# Mainland_revB.net
KiCad netlist of a schematic drawn in EAGLE
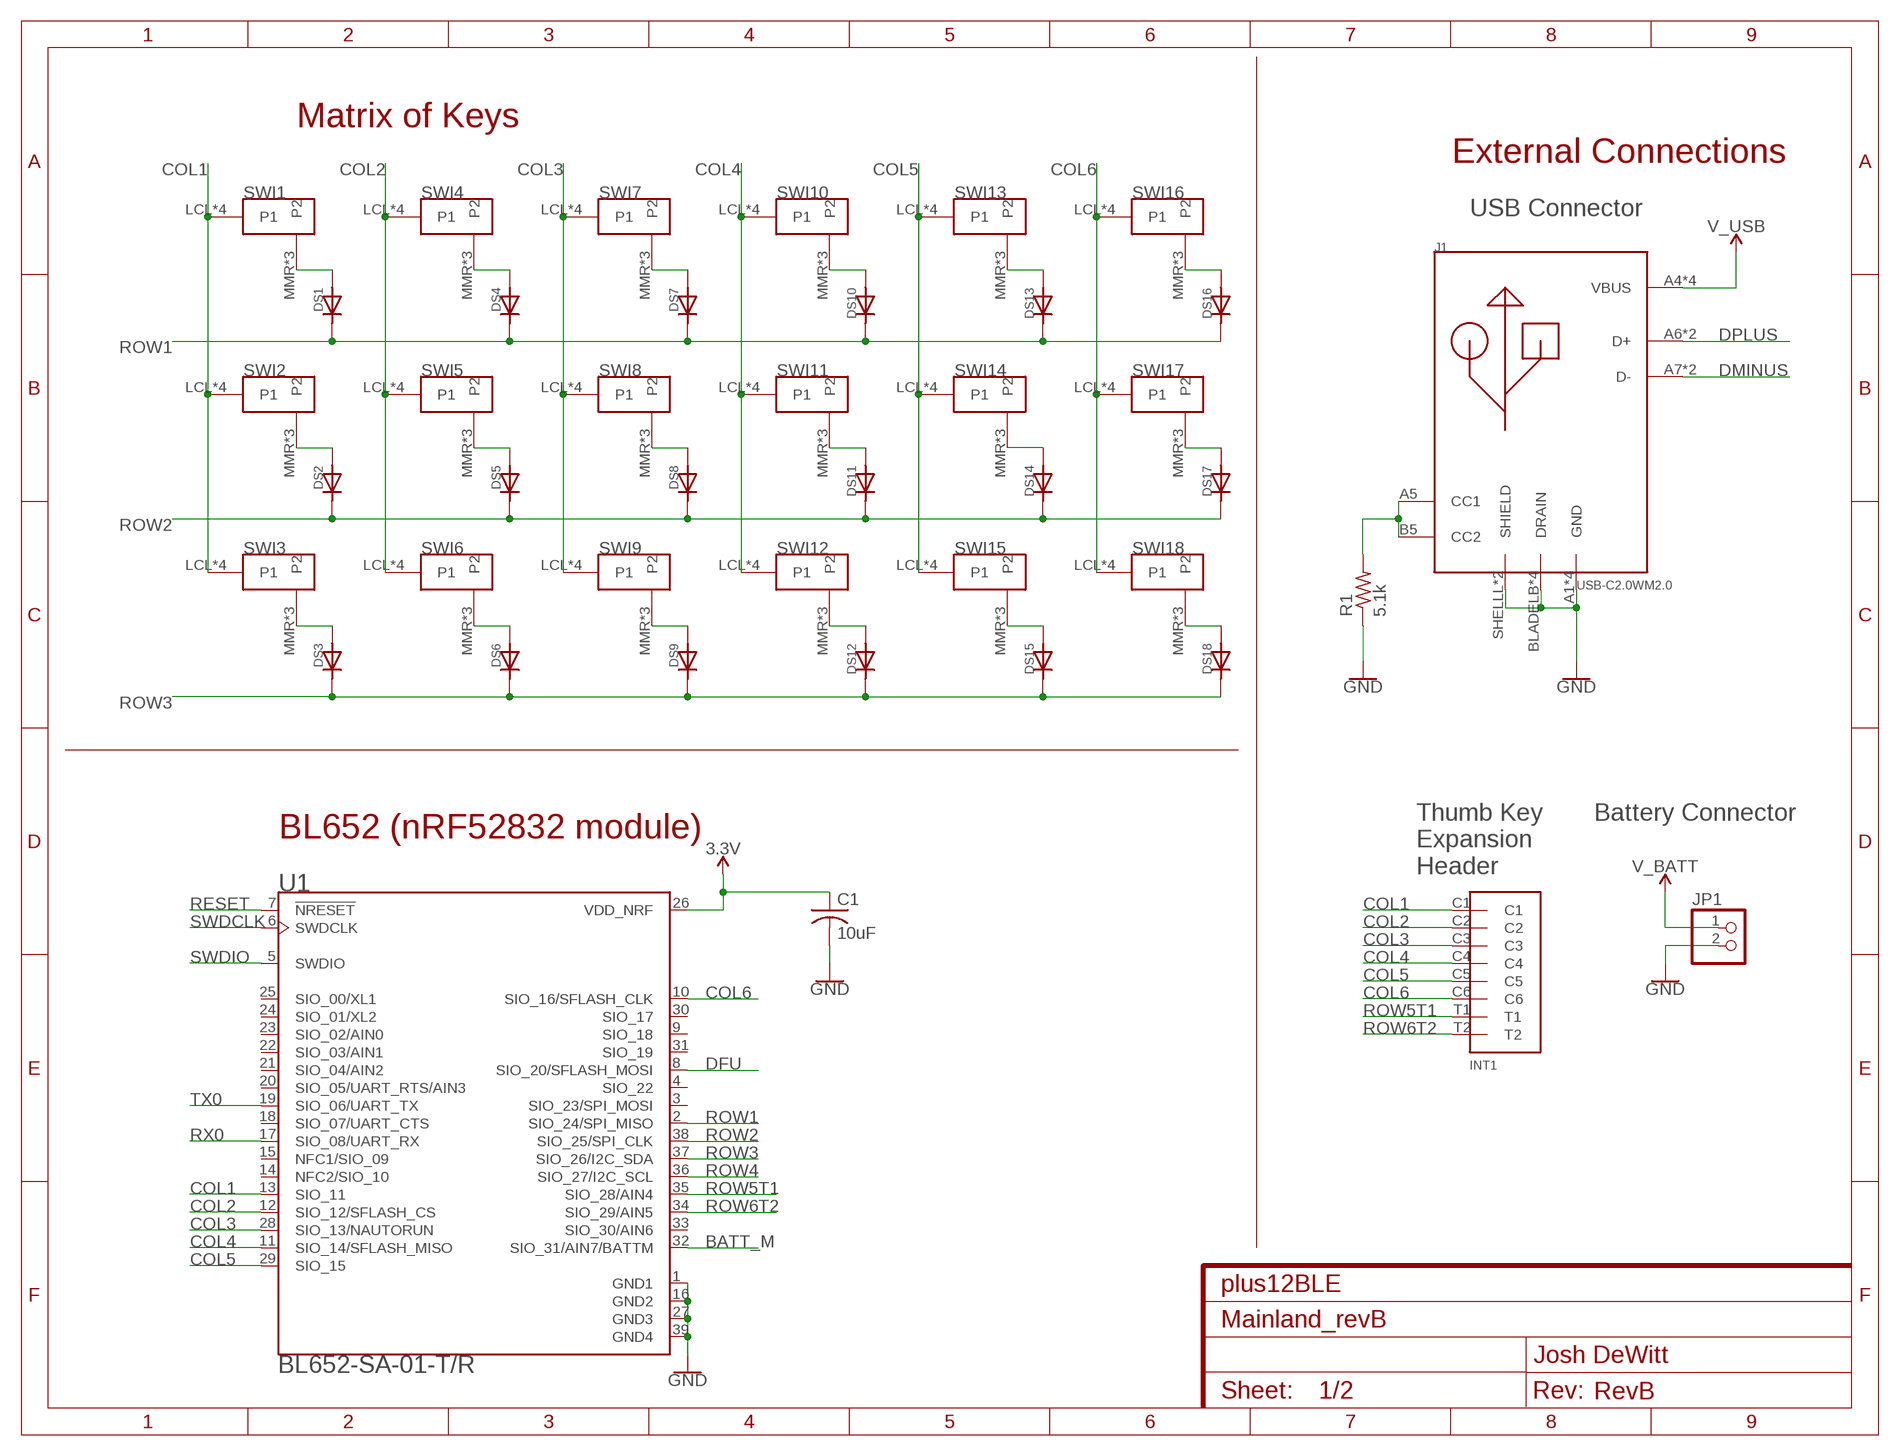
[diagram p0: schematic, sheet 1]
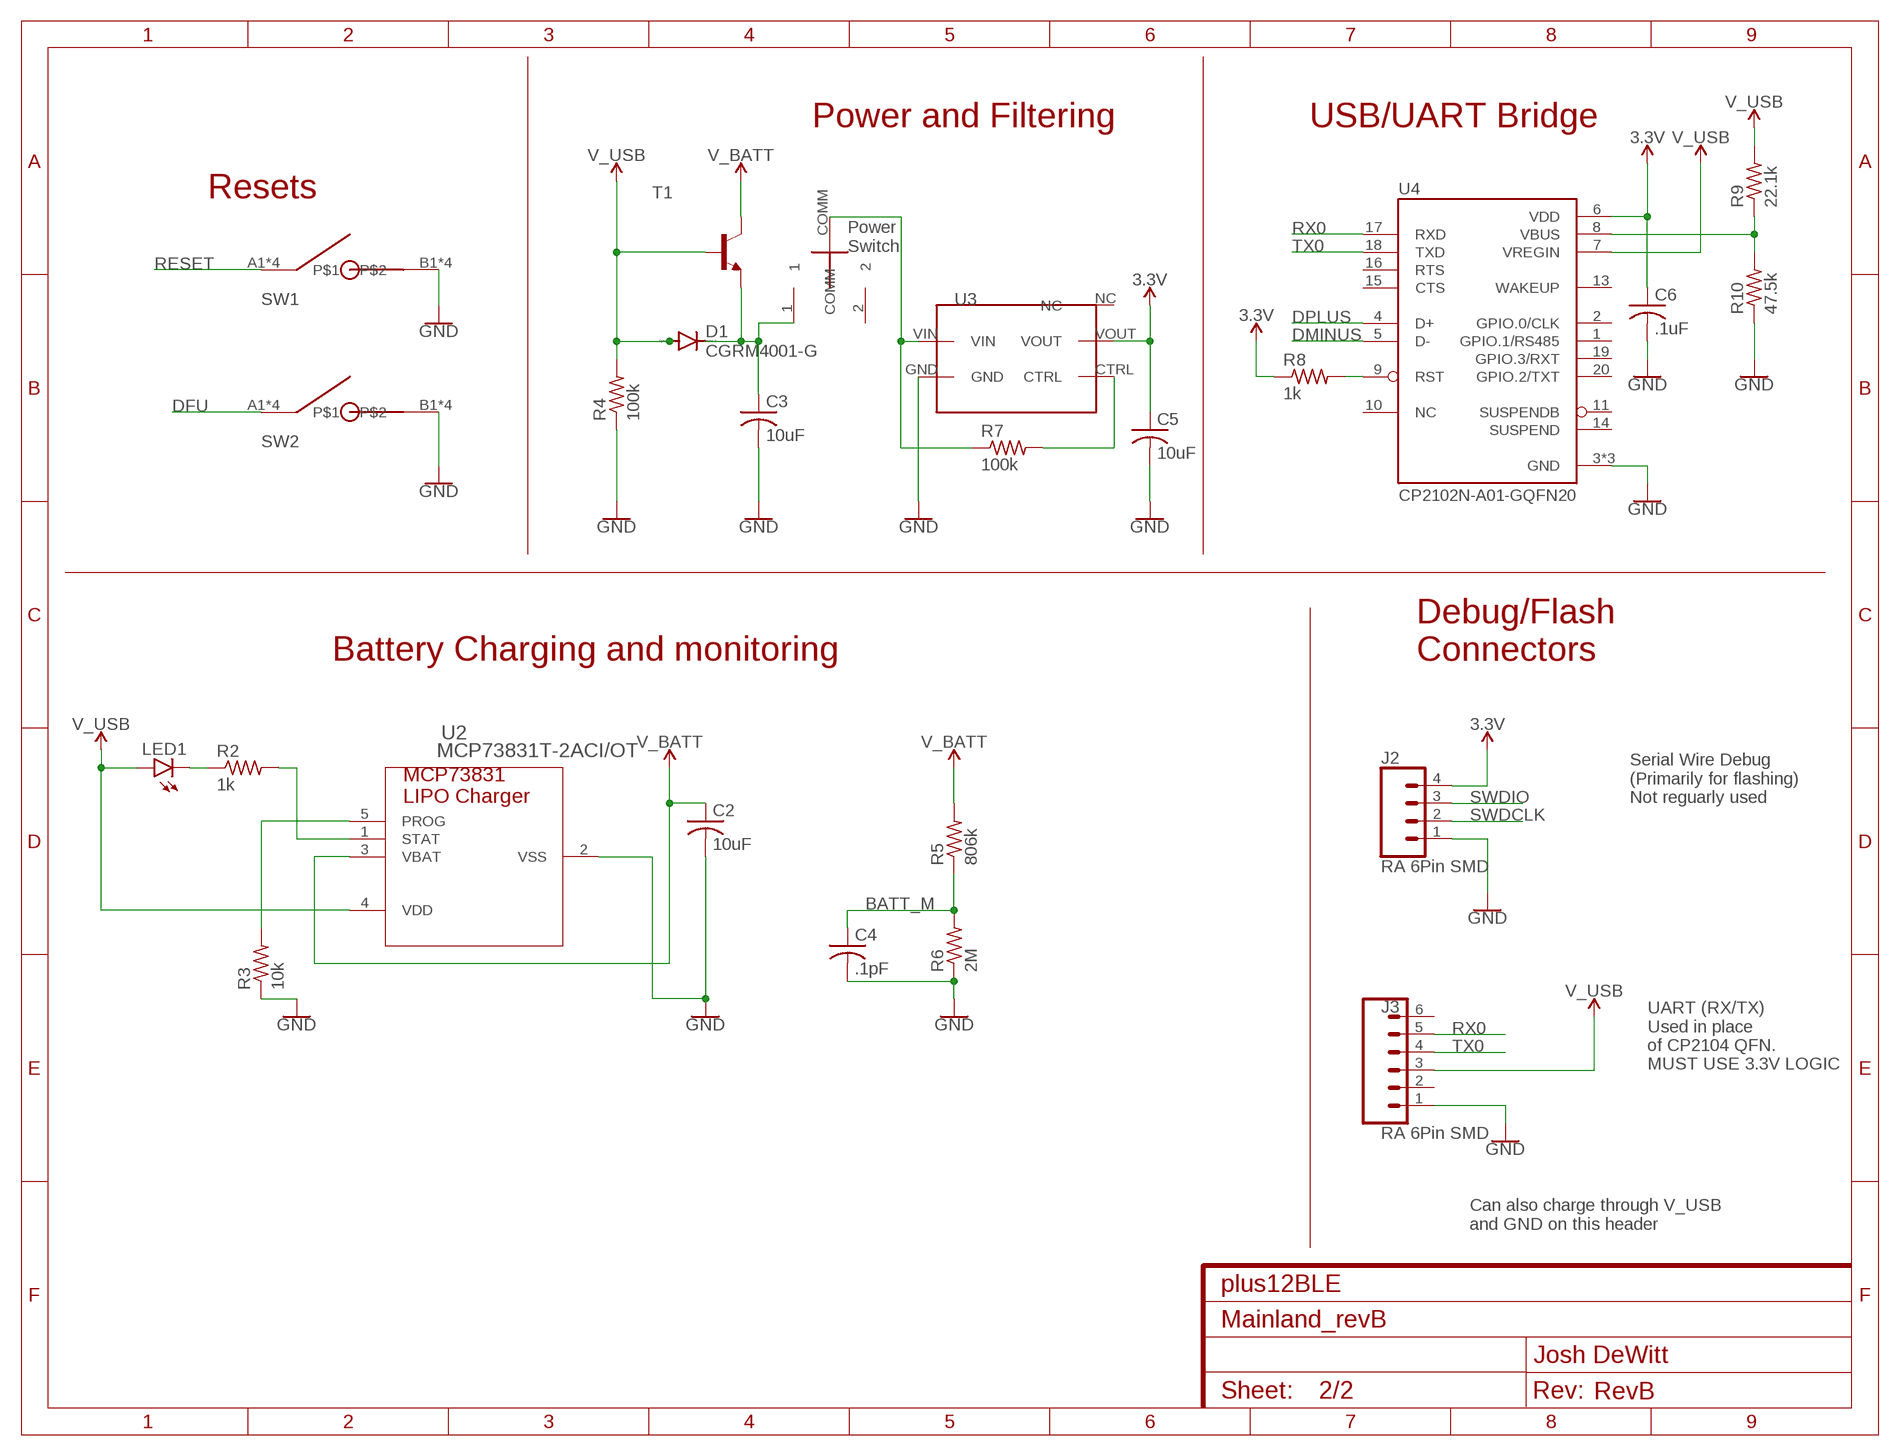
[diagram p1: schematic, sheet 2]

(export (version "E")
  (design (tool "Eeschema 10.0.6"))
  (components
    (comp (ref "C1")
      (value "10uF")
      (footprint "eagle-import:C0805K")
      (libsource (lib "eagle-import") (part "C-USC0805K"))
    )
    (comp (ref "DS1")
      (value "DIODECOMBO")
      (footprint "eagle-import:DIODE_COMBO")
      (libsource (lib "eagle-import") (part "DIODECOMBO"))
    )
    (comp (ref "DS2")
      (value "DIODECOMBO")
      (footprint "eagle-import:DIODE_COMBO")
      (libsource (lib "eagle-import") (part "DIODECOMBO"))
    )
    (comp (ref "DS3")
      (value "DIODECOMBO")
      (footprint "eagle-import:DIODE_COMBO")
      (libsource (lib "eagle-import") (part "DIODECOMBO"))
    )
    (comp (ref "DS4")
      (value "DIODECOMBO")
      (footprint "eagle-import:DIODE_COMBO")
      (libsource (lib "eagle-import") (part "DIODECOMBO"))
    )
    (comp (ref "DS5")
      (value "DIODECOMBO")
      (footprint "eagle-import:DIODE_COMBO")
      (libsource (lib "eagle-import") (part "DIODECOMBO"))
    )
    (comp (ref "DS6")
      (value "DIODECOMBO")
      (footprint "eagle-import:DIODE_COMBO")
      (libsource (lib "eagle-import") (part "DIODECOMBO"))
    )
    (comp (ref "DS7")
      (value "DIODECOMBO")
      (footprint "eagle-import:DIODE_COMBO")
      (libsource (lib "eagle-import") (part "DIODECOMBO"))
    )
    (comp (ref "DS8")
      (value "DIODECOMBO")
      (footprint "eagle-import:DIODE_COMBO")
      (libsource (lib "eagle-import") (part "DIODECOMBO"))
    )
    (comp (ref "DS9")
      (value "DIODECOMBO")
      (footprint "eagle-import:DIODE_COMBO")
      (libsource (lib "eagle-import") (part "DIODECOMBO"))
    )
    (comp (ref "DS10")
      (value "DIODECOMBO")
      (footprint "eagle-import:DIODE_COMBO")
      (libsource (lib "eagle-import") (part "DIODECOMBO"))
    )
    (comp (ref "DS11")
      (value "DIODECOMBO")
      (footprint "eagle-import:DIODE_COMBO")
      (libsource (lib "eagle-import") (part "DIODECOMBO"))
    )
    (comp (ref "DS12")
      (value "DIODECOMBO")
      (footprint "eagle-import:DIODE_COMBO")
      (libsource (lib "eagle-import") (part "DIODECOMBO"))
    )
    (comp (ref "DS13")
      (value "DIODECOMBO")
      (footprint "eagle-import:DIODE_COMBO")
      (libsource (lib "eagle-import") (part "DIODECOMBO"))
    )
    (comp (ref "DS14")
      (value "DIODECOMBO")
      (footprint "eagle-import:DIODE_COMBO")
      (libsource (lib "eagle-import") (part "DIODECOMBO"))
    )
    (comp (ref "DS15")
      (value "DIODECOMBO")
      (footprint "eagle-import:DIODE_COMBO")
      (libsource (lib "eagle-import") (part "DIODECOMBO"))
    )
    (comp (ref "DS16")
      (value "DIODECOMBO")
      (footprint "eagle-import:DIODE_COMBO")
      (libsource (lib "eagle-import") (part "DIODECOMBO"))
    )
    (comp (ref "DS17")
      (value "DIODECOMBO")
      (footprint "eagle-import:DIODE_COMBO")
      (libsource (lib "eagle-import") (part "DIODECOMBO"))
    )
    (comp (ref "DS18")
      (value "DIODECOMBO")
      (footprint "eagle-import:DIODE_COMBO")
      (libsource (lib "eagle-import") (part "DIODECOMBO"))
    )
    (comp (ref "FRAME1")
      (value "FRAME_LTR_CU_MARK")
      (footprint "eagle-import:FR-LTR-ON-PCB")
      (libsource (lib "eagle-import") (part "FRAME_LTR_CU_MARK"))
    )
    (comp (ref "INT1")
      (value "INTRCNNT4X2")
      (footprint "eagle-import:INTRRIBBON")
      (libsource (lib "eagle-import") (part "INTRCNNT4X2"))
    )
    (comp (ref "J1")
      (value "USB-C2.0WM2.0")
      (footprint "eagle-import:WM17904_SIMP")
      (libsource (lib "eagle-import") (part "USB-C2.0WM2.0"))
    )
    (comp (ref "JP1")
      (value "PINHD-1X2")
      (footprint "eagle-import:1X02")
      (libsource (lib "eagle-import") (part "PINHD-1X2"))
    )
    (comp (ref "R1")
      (value "5.1k")
      (footprint "eagle-import:R0603")
      (libsource (lib "eagle-import") (part "R-US_R0603"))
    )
    (comp (ref "SWI1")
      (value "MX/ALPSDOUBLE_SLOT")
      (footprint "eagle-import:DOUBLED_SLOTS")
      (libsource (lib "eagle-import") (part "MX/ALPSDOUBLE_SLOT"))
    )
    (comp (ref "SWI2")
      (value "MX/ALPSDOUBLE_SLOT")
      (footprint "eagle-import:DOUBLED_SLOTS")
      (libsource (lib "eagle-import") (part "MX/ALPSDOUBLE_SLOT"))
    )
    (comp (ref "SWI3")
      (value "MX/ALPSDOUBLE_SLOT")
      (footprint "eagle-import:DOUBLED_SLOTS")
      (libsource (lib "eagle-import") (part "MX/ALPSDOUBLE_SLOT"))
    )
    (comp (ref "SWI4")
      (value "MX/ALPSDOUBLE_SLOT")
      (footprint "eagle-import:DOUBLED_SLOTS")
      (libsource (lib "eagle-import") (part "MX/ALPSDOUBLE_SLOT"))
    )
    (comp (ref "SWI5")
      (value "MX/ALPSDOUBLE_SLOT")
      (footprint "eagle-import:DOUBLED_SLOTS")
      (libsource (lib "eagle-import") (part "MX/ALPSDOUBLE_SLOT"))
    )
    (comp (ref "SWI6")
      (value "MX/ALPSDOUBLE_SLOT")
      (footprint "eagle-import:DOUBLED_SLOTS")
      (libsource (lib "eagle-import") (part "MX/ALPSDOUBLE_SLOT"))
    )
    (comp (ref "SWI7")
      (value "MX/ALPSDOUBLE_SLOT")
      (footprint "eagle-import:DOUBLED_SLOTS")
      (libsource (lib "eagle-import") (part "MX/ALPSDOUBLE_SLOT"))
    )
    (comp (ref "SWI8")
      (value "MX/ALPSDOUBLE_SLOT")
      (footprint "eagle-import:DOUBLED_SLOTS")
      (libsource (lib "eagle-import") (part "MX/ALPSDOUBLE_SLOT"))
    )
    (comp (ref "SWI9")
      (value "MX/ALPSDOUBLE_SLOT")
      (footprint "eagle-import:DOUBLED_SLOTS")
      (libsource (lib "eagle-import") (part "MX/ALPSDOUBLE_SLOT"))
    )
    (comp (ref "SWI10")
      (value "MX/ALPSDOUBLE_SLOT")
      (footprint "eagle-import:DOUBLED_SLOTS")
      (libsource (lib "eagle-import") (part "MX/ALPSDOUBLE_SLOT"))
    )
    (comp (ref "SWI11")
      (value "MX/ALPSDOUBLE_SLOT")
      (footprint "eagle-import:DOUBLED_SLOTS")
      (libsource (lib "eagle-import") (part "MX/ALPSDOUBLE_SLOT"))
    )
    (comp (ref "SWI12")
      (value "MX/ALPSDOUBLE_SLOT")
      (footprint "eagle-import:DOUBLED_SLOTS")
      (libsource (lib "eagle-import") (part "MX/ALPSDOUBLE_SLOT"))
    )
    (comp (ref "SWI13")
      (value "MX/ALPSDOUBLE_SLOT")
      (footprint "eagle-import:DOUBLED_SLOTS")
      (libsource (lib "eagle-import") (part "MX/ALPSDOUBLE_SLOT"))
    )
    (comp (ref "SWI14")
      (value "MX/ALPSDOUBLE_SLOT")
      (footprint "eagle-import:DOUBLED_SLOTS")
      (libsource (lib "eagle-import") (part "MX/ALPSDOUBLE_SLOT"))
    )
    (comp (ref "SWI15")
      (value "MX/ALPSDOUBLE_SLOT")
      (footprint "eagle-import:DOUBLED_SLOTS")
      (libsource (lib "eagle-import") (part "MX/ALPSDOUBLE_SLOT"))
    )
    (comp (ref "SWI16")
      (value "MX/ALPSDOUBLE_SLOT")
      (footprint "eagle-import:DOUBLED_SLOTS")
      (libsource (lib "eagle-import") (part "MX/ALPSDOUBLE_SLOT"))
    )
    (comp (ref "SWI17")
      (value "MX/ALPSDOUBLE_SLOT")
      (footprint "eagle-import:DOUBLED_SLOTS")
      (libsource (lib "eagle-import") (part "MX/ALPSDOUBLE_SLOT"))
    )
    (comp (ref "SWI18")
      (value "MX/ALPSDOUBLE_SLOT")
      (footprint "eagle-import:DOUBLED_SLOTS")
      (libsource (lib "eagle-import") (part "MX/ALPSDOUBLE_SLOT"))
    )
    (comp (ref "U1")
      (value "BL652-SA-01-T/R")
      (footprint "eagle-import:XCVR_BL652-SA-01-T_R")
      (fields (field (name "DIGI-KEY_PART_NUMBER") "BL652-SA-01-CT-ND") (field (name "MF") "Laird -"))
      (libsource (lib "eagle-import") (part "BL652-SA-01-T/R"))
    )
    (comp (ref "C2")
      (value "10uF")
      (footprint "eagle-import:C0805K")
      (libsource (lib "eagle-import") (part "C-USC0805K"))
    )
    (comp (ref "C3")
      (value "10uF")
      (footprint "eagle-import:C0805K")
      (libsource (lib "eagle-import") (part "C-USC0805K"))
    )
    (comp (ref "C4")
      (value ".1pF")
      (footprint "eagle-import:C0603")
      (libsource (lib "eagle-import") (part "C-USC0603"))
    )
    (comp (ref "C5")
      (value "10uF")
      (footprint "eagle-import:C0805K")
      (libsource (lib "eagle-import") (part "C-USC0805K"))
    )
    (comp (ref "C6")
      (value ".1uF")
      (footprint "eagle-import:C0603")
      (libsource (lib "eagle-import") (part "C-USC0603"))
    )
    (comp (ref "D1")
      (value "CGRM4001-G")
      (footprint "eagle-import:SOD-123_MINI-SMA")
      (libsource (lib "eagle-import") (part "CGRM400-G1"))
    )
    (comp (ref "FRAME2")
      (value "FRAME_LTR_CU_MARK")
      (footprint "eagle-import:FR-LTR-ON-PCB")
      (libsource (lib "eagle-import") (part "FRAME_LTR_CU_MARK"))
    )
    (comp (ref "J2")
      (value "RA 6Pin SMD")
      (footprint "eagle-import:1X04_SMD_RA_FEMALE")
      (libsource (lib "eagle-import") (part "CONN_04SMD_RA_FEMALE"))
    )
    (comp (ref "J3")
      (value "RA 6Pin SMD")
      (footprint "eagle-import:1X06-SMD_RA_MALE")
      (libsource (lib "eagle-import") (part "CONN_06SMD"))
    )
    (comp (ref "LED1")
      (value "LEDCHIP-LED0603")
      (footprint "eagle-import:CHIP-LED0603")
      (libsource (lib "eagle-import") (part "LEDCHIP-LED0603"))
    )
    (comp (ref "R2")
      (value "1k")
      (footprint "eagle-import:R0603")
      (libsource (lib "eagle-import") (part "R-US_R0603"))
    )
    (comp (ref "R3")
      (value "10k")
      (footprint "eagle-import:R0603")
      (libsource (lib "eagle-import") (part "R-US_R0603"))
    )
    (comp (ref "R4")
      (value "100k")
      (footprint "eagle-import:R0603")
      (libsource (lib "eagle-import") (part "R-US_R0603"))
    )
    (comp (ref "R5")
      (value "806k")
      (footprint "eagle-import:R0603")
      (libsource (lib "eagle-import") (part "R-US_R0603"))
    )
    (comp (ref "R6")
      (value "2M")
      (footprint "eagle-import:R0603")
      (libsource (lib "eagle-import") (part "R-US_R0603"))
    )
    (comp (ref "R7")
      (value "100k")
      (footprint "eagle-import:R0603")
      (libsource (lib "eagle-import") (part "R-US_R0603"))
    )
    (comp (ref "R8")
      (value "1k")
      (footprint "eagle-import:R0603")
      (libsource (lib "eagle-import") (part "R-US_R0603"))
    )
    (comp (ref "R9")
      (value "22.1k")
      (footprint "eagle-import:R0603")
      (libsource (lib "eagle-import") (part "R-US_R0603"))
    )
    (comp (ref "R10")
      (value "47.5k")
      (footprint "eagle-import:R0603")
      (libsource (lib "eagle-import") (part "R-US_R0603"))
    )
    (comp (ref "SW1")
      (value "RSTSWSMALL_SMD")
      (footprint "eagle-import:EVP-BBA")
      (libsource (lib "eagle-import") (part "RSTSWSMALL_SMD"))
    )
    (comp (ref "SW2")
      (value "RSTSWSMALL_SMD")
      (footprint "eagle-import:EVP-BBA")
      (libsource (lib "eagle-import") (part "RSTSWSMALL_SMD"))
    )
    (comp (ref "SW3")
      (value "SLIDER_SWITCH")
      (footprint "eagle-import:MHSS1105")
      (libsource (lib "eagle-import") (part "SLIDER_SWITCH"))
    )
    (comp (ref "T1")
      (value "BC808-NPN-SOT23-BEC")
      (footprint "eagle-import:SOT23-BEC")
      (libsource (lib "eagle-import") (part "-NPN-SOT23-BECBC808"))
    )
    (comp (ref "U2")
      (value "MCP73831T-2ACI/OT")
      (footprint "eagle-import:SOT-23-5_MC")
      (fields (field (name "MANUFACTURER_PART_NUMBER") "MCP73831T2ACIOT"))
      (libsource (lib "eagle-import") (part "MCP73831T-2ACI/OT"))
    )
    (comp (ref "U3")
      (value "TCR2EF")
      (footprint "eagle-import:TCR2EF")
      (libsource (lib "eagle-import") (part "TCR2EF"))
    )
    (comp (ref "U4")
      (value "CP2102N-A01-GQFN20")
      (footprint "eagle-import:SILABS_QFN20")
      (fields (field (name "DIGI-KEY_PART_NUMBER") "336-3692-ND") (field (name "MF") "Silicon Labs"))
      (libsource (lib "eagle-import") (part "CP2102N-A01-GQFN20"))
    )
  )
  (nets
    (net (code "1") (name "3.3V") (class "Default")
      (node (ref "C1") (pin "1") (pinfunction "1_1") (pintype "passive"))
      (node (ref "C5") (pin "1") (pinfunction "1_1") (pintype "passive"))
      (node (ref "C6") (pin "1") (pinfunction "1_1") (pintype "passive"))
      (node (ref "J2") (pin "4") (pinfunction "4_4") (pintype "passive"))
      (node (ref "R8") (pin "1") (pinfunction "1_1") (pintype "passive"))
      (node (ref "U1") (pin "26") (pinfunction "VDD_NRF_26") (pintype "power_in"))
      (node (ref "U3") (pin "VOUT") (pinfunction "VOUT_VOUT") (pintype "power_in"))
      (node (ref "U4") (pin "6") (pinfunction "VDD_6") (pintype "power_in"))
    )
    (net (code "2") (name "BATT_M") (class "Default")
      (node (ref "C4") (pin "1") (pinfunction "1_1") (pintype "passive"))
      (node (ref "R5") (pin "1") (pinfunction "1_1") (pintype "passive"))
      (node (ref "R6") (pin "2") (pinfunction "2_2") (pintype "passive"))
      (node (ref "U1") (pin "32") (pinfunction "SIO_31/AIN7/BATTM_32") (pintype "bidirectional"))
    )
    (net (code "3") (name "COL1") (class "Default")
      (node (ref "INT1") (pin "C1") (pinfunction "C1_C1") (pintype "bidirectional"))
      (node (ref "SWI1") (pin "LCL") (pinfunction "P1_LCL") (pintype "bidirectional"))
      (node (ref "SWI1") (pin "LLP") (pinfunction "P1_LLP") (pintype "bidirectional"))
      (node (ref "SWI1") (pin "LRLP") (pinfunction "P1_LRLP") (pintype "bidirectional"))
      (node (ref "SWI1") (pin "MML") (pinfunction "P1_MML") (pintype "bidirectional"))
      (node (ref "SWI2") (pin "LCL") (pinfunction "P1_LCL") (pintype "bidirectional"))
      (node (ref "SWI2") (pin "LLP") (pinfunction "P1_LLP") (pintype "bidirectional"))
      (node (ref "SWI2") (pin "LRLP") (pinfunction "P1_LRLP") (pintype "bidirectional"))
      (node (ref "SWI2") (pin "MML") (pinfunction "P1_MML") (pintype "bidirectional"))
      (node (ref "SWI3") (pin "LCL") (pinfunction "P1_LCL") (pintype "bidirectional"))
      (node (ref "SWI3") (pin "LLP") (pinfunction "P1_LLP") (pintype "bidirectional"))
      (node (ref "SWI3") (pin "LRLP") (pinfunction "P1_LRLP") (pintype "bidirectional"))
      (node (ref "SWI3") (pin "MML") (pinfunction "P1_MML") (pintype "bidirectional"))
      (node (ref "U1") (pin "13") (pinfunction "SIO_11_13") (pintype "bidirectional"))
    )
    (net (code "4") (name "COL2") (class "Default")
      (node (ref "INT1") (pin "C2") (pinfunction "C2_C2") (pintype "bidirectional"))
      (node (ref "SWI4") (pin "LCL") (pinfunction "P1_LCL") (pintype "bidirectional"))
      (node (ref "SWI4") (pin "LLP") (pinfunction "P1_LLP") (pintype "bidirectional"))
      (node (ref "SWI4") (pin "LRLP") (pinfunction "P1_LRLP") (pintype "bidirectional"))
      (node (ref "SWI4") (pin "MML") (pinfunction "P1_MML") (pintype "bidirectional"))
      (node (ref "SWI5") (pin "LCL") (pinfunction "P1_LCL") (pintype "bidirectional"))
      (node (ref "SWI5") (pin "LLP") (pinfunction "P1_LLP") (pintype "bidirectional"))
      (node (ref "SWI5") (pin "LRLP") (pinfunction "P1_LRLP") (pintype "bidirectional"))
      (node (ref "SWI5") (pin "MML") (pinfunction "P1_MML") (pintype "bidirectional"))
      (node (ref "SWI6") (pin "LCL") (pinfunction "P1_LCL") (pintype "bidirectional"))
      (node (ref "SWI6") (pin "LLP") (pinfunction "P1_LLP") (pintype "bidirectional"))
      (node (ref "SWI6") (pin "LRLP") (pinfunction "P1_LRLP") (pintype "bidirectional"))
      (node (ref "SWI6") (pin "MML") (pinfunction "P1_MML") (pintype "bidirectional"))
      (node (ref "U1") (pin "12") (pinfunction "SIO_12/SFLASH_CS_12") (pintype "bidirectional"))
    )
    (net (code "5") (name "COL3") (class "Default")
      (node (ref "INT1") (pin "C3") (pinfunction "C3_C3") (pintype "bidirectional"))
      (node (ref "SWI7") (pin "LCL") (pinfunction "P1_LCL") (pintype "bidirectional"))
      (node (ref "SWI7") (pin "LLP") (pinfunction "P1_LLP") (pintype "bidirectional"))
      (node (ref "SWI7") (pin "LRLP") (pinfunction "P1_LRLP") (pintype "bidirectional"))
      (node (ref "SWI7") (pin "MML") (pinfunction "P1_MML") (pintype "bidirectional"))
      (node (ref "SWI8") (pin "LCL") (pinfunction "P1_LCL") (pintype "bidirectional"))
      (node (ref "SWI8") (pin "LLP") (pinfunction "P1_LLP") (pintype "bidirectional"))
      (node (ref "SWI8") (pin "LRLP") (pinfunction "P1_LRLP") (pintype "bidirectional"))
      (node (ref "SWI8") (pin "MML") (pinfunction "P1_MML") (pintype "bidirectional"))
      (node (ref "SWI9") (pin "LCL") (pinfunction "P1_LCL") (pintype "bidirectional"))
      (node (ref "SWI9") (pin "LLP") (pinfunction "P1_LLP") (pintype "bidirectional"))
      (node (ref "SWI9") (pin "LRLP") (pinfunction "P1_LRLP") (pintype "bidirectional"))
      (node (ref "SWI9") (pin "MML") (pinfunction "P1_MML") (pintype "bidirectional"))
      (node (ref "U1") (pin "28") (pinfunction "SIO_13/NAUTORUN_28") (pintype "bidirectional"))
    )
    (net (code "6") (name "COL4") (class "Default")
      (node (ref "INT1") (pin "C4") (pinfunction "C4_C4") (pintype "bidirectional"))
      (node (ref "SWI10") (pin "LCL") (pinfunction "P1_LCL") (pintype "bidirectional"))
      (node (ref "SWI10") (pin "LLP") (pinfunction "P1_LLP") (pintype "bidirectional"))
      (node (ref "SWI10") (pin "LRLP") (pinfunction "P1_LRLP") (pintype "bidirectional"))
      (node (ref "SWI10") (pin "MML") (pinfunction "P1_MML") (pintype "bidirectional"))
      (node (ref "SWI11") (pin "LCL") (pinfunction "P1_LCL") (pintype "bidirectional"))
      (node (ref "SWI11") (pin "LLP") (pinfunction "P1_LLP") (pintype "bidirectional"))
      (node (ref "SWI11") (pin "LRLP") (pinfunction "P1_LRLP") (pintype "bidirectional"))
      (node (ref "SWI11") (pin "MML") (pinfunction "P1_MML") (pintype "bidirectional"))
      (node (ref "SWI12") (pin "LCL") (pinfunction "P1_LCL") (pintype "bidirectional"))
      (node (ref "SWI12") (pin "LLP") (pinfunction "P1_LLP") (pintype "bidirectional"))
      (node (ref "SWI12") (pin "LRLP") (pinfunction "P1_LRLP") (pintype "bidirectional"))
      (node (ref "SWI12") (pin "MML") (pinfunction "P1_MML") (pintype "bidirectional"))
      (node (ref "U1") (pin "11") (pinfunction "SIO_14/SFLASH_MISO_11") (pintype "bidirectional"))
    )
    (net (code "7") (name "COL5") (class "Default")
      (node (ref "INT1") (pin "C5") (pinfunction "C5_C5") (pintype "bidirectional"))
      (node (ref "SWI13") (pin "LCL") (pinfunction "P1_LCL") (pintype "bidirectional"))
      (node (ref "SWI13") (pin "LLP") (pinfunction "P1_LLP") (pintype "bidirectional"))
      (node (ref "SWI13") (pin "LRLP") (pinfunction "P1_LRLP") (pintype "bidirectional"))
      (node (ref "SWI13") (pin "MML") (pinfunction "P1_MML") (pintype "bidirectional"))
      (node (ref "SWI14") (pin "LCL") (pinfunction "P1_LCL") (pintype "bidirectional"))
      (node (ref "SWI14") (pin "LLP") (pinfunction "P1_LLP") (pintype "bidirectional"))
      (node (ref "SWI14") (pin "LRLP") (pinfunction "P1_LRLP") (pintype "bidirectional"))
      (node (ref "SWI14") (pin "MML") (pinfunction "P1_MML") (pintype "bidirectional"))
      (node (ref "SWI15") (pin "LCL") (pinfunction "P1_LCL") (pintype "bidirectional"))
      (node (ref "SWI15") (pin "LLP") (pinfunction "P1_LLP") (pintype "bidirectional"))
      (node (ref "SWI15") (pin "LRLP") (pinfunction "P1_LRLP") (pintype "bidirectional"))
      (node (ref "SWI15") (pin "MML") (pinfunction "P1_MML") (pintype "bidirectional"))
      (node (ref "U1") (pin "29") (pinfunction "SIO_15_29") (pintype "bidirectional"))
    )
    (net (code "8") (name "COL6") (class "Default")
      (node (ref "INT1") (pin "C6") (pinfunction "C6_C6") (pintype "bidirectional"))
      (node (ref "SWI16") (pin "LCL") (pinfunction "P1_LCL") (pintype "bidirectional"))
      (node (ref "SWI16") (pin "LLP") (pinfunction "P1_LLP") (pintype "bidirectional"))
      (node (ref "SWI16") (pin "LRLP") (pinfunction "P1_LRLP") (pintype "bidirectional"))
      (node (ref "SWI16") (pin "MML") (pinfunction "P1_MML") (pintype "bidirectional"))
      (node (ref "SWI17") (pin "LCL") (pinfunction "P1_LCL") (pintype "bidirectional"))
      (node (ref "SWI17") (pin "LLP") (pinfunction "P1_LLP") (pintype "bidirectional"))
      (node (ref "SWI17") (pin "LRLP") (pinfunction "P1_LRLP") (pintype "bidirectional"))
      (node (ref "SWI17") (pin "MML") (pinfunction "P1_MML") (pintype "bidirectional"))
      (node (ref "SWI18") (pin "LCL") (pinfunction "P1_LCL") (pintype "bidirectional"))
      (node (ref "SWI18") (pin "LLP") (pinfunction "P1_LLP") (pintype "bidirectional"))
      (node (ref "SWI18") (pin "LRLP") (pinfunction "P1_LRLP") (pintype "bidirectional"))
      (node (ref "SWI18") (pin "MML") (pinfunction "P1_MML") (pintype "bidirectional"))
      (node (ref "U1") (pin "10") (pinfunction "SIO_16/SFLASH_CLK_10") (pintype "bidirectional"))
    )
    (net (code "9") (name "DFU") (class "Default")
      (node (ref "SW2") (pin "A1") (pinfunction "P$1_A1") (pintype "bidirectional"))
      (node (ref "SW2") (pin "A2") (pinfunction "P$1_A2") (pintype "bidirectional"))
      (node (ref "SW2") (pin "A3") (pinfunction "P$1_A3") (pintype "bidirectional"))
      (node (ref "SW2") (pin "A4") (pinfunction "P$1_A4") (pintype "bidirectional"))
      (node (ref "U1") (pin "8") (pinfunction "SIO_20/SFLASH_MOSI_8") (pintype "bidirectional"))
    )
    (net (code "10") (name "DMINUS") (class "Default")
      (node (ref "J1") (pin "A7") (pinfunction "D-_A7") (pintype "bidirectional"))
      (node (ref "J1") (pin "B7") (pinfunction "D-_B7") (pintype "bidirectional"))
      (node (ref "U4") (pin "5") (pinfunction "D-_5") (pintype "bidirectional"))
    )
    (net (code "11") (name "DPLUS") (class "Default")
      (node (ref "J1") (pin "A6") (pinfunction "D+_A6") (pintype "bidirectional"))
      (node (ref "J1") (pin "B6") (pinfunction "D+_B6") (pintype "bidirectional"))
      (node (ref "U4") (pin "4") (pinfunction "D+_4") (pintype "bidirectional"))
    )
    (net (code "12") (name "GND") (class "Default")
      (node (ref "C1") (pin "2") (pinfunction "2_2") (pintype "passive"))
      (node (ref "C2") (pin "2") (pinfunction "2_2") (pintype "passive"))
      (node (ref "C3") (pin "2") (pinfunction "2_2") (pintype "passive"))
      (node (ref "C4") (pin "2") (pinfunction "2_2") (pintype "passive"))
      (node (ref "C5") (pin "2") (pinfunction "2_2") (pintype "passive"))
      (node (ref "C6") (pin "2") (pinfunction "2_2") (pintype "passive"))
      (node (ref "J1") (pin "A1") (pinfunction "GND_A1") (pintype "bidirectional"))
      (node (ref "J1") (pin "A12") (pinfunction "GND_A12") (pintype "bidirectional"))
      (node (ref "J1") (pin "B1") (pinfunction "GND_B1") (pintype "bidirectional"))
      (node (ref "J1") (pin "B12") (pinfunction "GND_B12") (pintype "bidirectional"))
      (node (ref "J1") (pin "BLADELB") (pinfunction "DRAIN_BLADELB") (pintype "bidirectional"))
      (node (ref "J1") (pin "BLADELF") (pinfunction "DRAIN_BLADELF") (pintype "bidirectional"))
      (node (ref "J1") (pin "BLADERB") (pinfunction "DRAIN_BLADERB") (pintype "bidirectional"))
      (node (ref "J1") (pin "BLADERF") (pinfunction "DRAIN_BLADERF") (pintype "bidirectional"))
      (node (ref "J1") (pin "SHELLL") (pinfunction "SHIELD_SHELLL") (pintype "bidirectional"))
      (node (ref "J1") (pin "SHELLR") (pinfunction "SHIELD_SHELLR") (pintype "bidirectional"))
      (node (ref "J2") (pin "1") (pinfunction "1_1") (pintype "passive"))
      (node (ref "J3") (pin "1") (pinfunction "1_1") (pintype "passive"))
      (node (ref "JP1") (pin "2") (pinfunction "2_2") (pintype "passive"))
      (node (ref "R1") (pin "1") (pinfunction "1_1") (pintype "passive"))
      (node (ref "R10") (pin "1") (pinfunction "1_1") (pintype "passive"))
      (node (ref "R3") (pin "1") (pinfunction "1_1") (pintype "passive"))
      (node (ref "R4") (pin "1") (pinfunction "1_1") (pintype "passive"))
      (node (ref "R6") (pin "1") (pinfunction "1_1") (pintype "passive"))
      (node (ref "SW1") (pin "B1") (pinfunction "P$2_B1") (pintype "bidirectional"))
      (node (ref "SW1") (pin "B2") (pinfunction "P$2_B2") (pintype "bidirectional"))
      (node (ref "SW1") (pin "B3") (pinfunction "P$2_B3") (pintype "bidirectional"))
      (node (ref "SW1") (pin "B4") (pinfunction "P$2_B4") (pintype "bidirectional"))
      (node (ref "SW2") (pin "B1") (pinfunction "P$2_B1") (pintype "bidirectional"))
      (node (ref "SW2") (pin "B2") (pinfunction "P$2_B2") (pintype "bidirectional"))
      (node (ref "SW2") (pin "B3") (pinfunction "P$2_B3") (pintype "bidirectional"))
      (node (ref "SW2") (pin "B4") (pinfunction "P$2_B4") (pintype "bidirectional"))
      (node (ref "U1") (pin "1") (pinfunction "GND1_1") (pintype "power_in"))
      (node (ref "U1") (pin "16") (pinfunction "GND2_16") (pintype "power_in"))
      (node (ref "U1") (pin "27") (pinfunction "GND3_27") (pintype "power_in"))
      (node (ref "U1") (pin "39") (pinfunction "GND4_39") (pintype "power_in"))
      (node (ref "U2") (pin "2") (pinfunction "VSS_2") (pintype "passive"))
      (node (ref "U3") (pin "GND") (pinfunction "GND_GND") (pintype "power_in"))
      (node (ref "U4") (pin "12") (pinfunction "GND_12") (pintype "power_in"))
      (node (ref "U4") (pin "21") (pinfunction "GND_21") (pintype "power_in"))
      (node (ref "U4") (pin "3") (pinfunction "GND_3") (pintype "power_in"))
    )
    (net (code "13") (name "Net-(C3-Pad1)") (class "Default")
      (node (ref "C3") (pin "1") (pinfunction "1_1") (pintype "passive"))
      (node (ref "D1") (pin "C") (pinfunction "C_C") (pintype "passive"))
      (node (ref "SW3") (pin "1") (pinfunction "1_1") (pintype "passive"))
      (node (ref "T1") (pin "E") (pinfunction "E_E") (pintype "passive"))
    )
    (net (code "14") (name "Net-(DS1-AN-PadANOST)") (class "Default")
      (node (ref "DS1") (pin "ANOST") (pinfunction "AN_ANOST") (pintype "bidirectional"))
      (node (ref "DS1") (pin "ANOT") (pinfunction "AN_ANOT") (pintype "bidirectional"))
      (node (ref "SWI1") (pin "MMR") (pinfunction "P2_MMR") (pintype "bidirectional"))
      (node (ref "SWI1") (pin "RCL") (pinfunction "P2_RCL") (pintype "bidirectional"))
      (node (ref "SWI1") (pin "RLMID") (pinfunction "P2_RLMID") (pintype "bidirectional"))
    )
    (net (code "15") (name "Net-(DS2-AN-PadANOST)") (class "Default")
      (node (ref "DS2") (pin "ANOST") (pinfunction "AN_ANOST") (pintype "bidirectional"))
      (node (ref "DS2") (pin "ANOT") (pinfunction "AN_ANOT") (pintype "bidirectional"))
      (node (ref "SWI2") (pin "MMR") (pinfunction "P2_MMR") (pintype "bidirectional"))
      (node (ref "SWI2") (pin "RCL") (pinfunction "P2_RCL") (pintype "bidirectional"))
      (node (ref "SWI2") (pin "RLMID") (pinfunction "P2_RLMID") (pintype "bidirectional"))
    )
    (net (code "16") (name "Net-(DS3-AN-PadANOST)") (class "Default")
      (node (ref "DS3") (pin "ANOST") (pinfunction "AN_ANOST") (pintype "bidirectional"))
      (node (ref "DS3") (pin "ANOT") (pinfunction "AN_ANOT") (pintype "bidirectional"))
      (node (ref "SWI3") (pin "MMR") (pinfunction "P2_MMR") (pintype "bidirectional"))
      (node (ref "SWI3") (pin "RCL") (pinfunction "P2_RCL") (pintype "bidirectional"))
      (node (ref "SWI3") (pin "RLMID") (pinfunction "P2_RLMID") (pintype "bidirectional"))
    )
    (net (code "17") (name "Net-(DS4-AN-PadANOST)") (class "Default")
      (node (ref "DS4") (pin "ANOST") (pinfunction "AN_ANOST") (pintype "bidirectional"))
      (node (ref "DS4") (pin "ANOT") (pinfunction "AN_ANOT") (pintype "bidirectional"))
      (node (ref "SWI4") (pin "MMR") (pinfunction "P2_MMR") (pintype "bidirectional"))
      (node (ref "SWI4") (pin "RCL") (pinfunction "P2_RCL") (pintype "bidirectional"))
      (node (ref "SWI4") (pin "RLMID") (pinfunction "P2_RLMID") (pintype "bidirectional"))
    )
    (net (code "18") (name "Net-(DS5-AN-PadANOST)") (class "Default")
      (node (ref "DS5") (pin "ANOST") (pinfunction "AN_ANOST") (pintype "bidirectional"))
      (node (ref "DS5") (pin "ANOT") (pinfunction "AN_ANOT") (pintype "bidirectional"))
      (node (ref "SWI5") (pin "MMR") (pinfunction "P2_MMR") (pintype "bidirectional"))
      (node (ref "SWI5") (pin "RCL") (pinfunction "P2_RCL") (pintype "bidirectional"))
      (node (ref "SWI5") (pin "RLMID") (pinfunction "P2_RLMID") (pintype "bidirectional"))
    )
    (net (code "19") (name "Net-(DS6-AN-PadANOST)") (class "Default")
      (node (ref "DS6") (pin "ANOST") (pinfunction "AN_ANOST") (pintype "bidirectional"))
      (node (ref "DS6") (pin "ANOT") (pinfunction "AN_ANOT") (pintype "bidirectional"))
      (node (ref "SWI6") (pin "MMR") (pinfunction "P2_MMR") (pintype "bidirectional"))
      (node (ref "SWI6") (pin "RCL") (pinfunction "P2_RCL") (pintype "bidirectional"))
      (node (ref "SWI6") (pin "RLMID") (pinfunction "P2_RLMID") (pintype "bidirectional"))
    )
    (net (code "20") (name "Net-(DS7-AN-PadANOST)") (class "Default")
      (node (ref "DS7") (pin "ANOST") (pinfunction "AN_ANOST") (pintype "bidirectional"))
      (node (ref "DS7") (pin "ANOT") (pinfunction "AN_ANOT") (pintype "bidirectional"))
      (node (ref "SWI7") (pin "MMR") (pinfunction "P2_MMR") (pintype "bidirectional"))
      (node (ref "SWI7") (pin "RCL") (pinfunction "P2_RCL") (pintype "bidirectional"))
      (node (ref "SWI7") (pin "RLMID") (pinfunction "P2_RLMID") (pintype "bidirectional"))
    )
    (net (code "21") (name "Net-(DS8-AN-PadANOST)") (class "Default")
      (node (ref "DS8") (pin "ANOST") (pinfunction "AN_ANOST") (pintype "bidirectional"))
      (node (ref "DS8") (pin "ANOT") (pinfunction "AN_ANOT") (pintype "bidirectional"))
      (node (ref "SWI8") (pin "MMR") (pinfunction "P2_MMR") (pintype "bidirectional"))
      (node (ref "SWI8") (pin "RCL") (pinfunction "P2_RCL") (pintype "bidirectional"))
      (node (ref "SWI8") (pin "RLMID") (pinfunction "P2_RLMID") (pintype "bidirectional"))
    )
    (net (code "22") (name "Net-(DS9-AN-PadANOST)") (class "Default")
      (node (ref "DS9") (pin "ANOST") (pinfunction "AN_ANOST") (pintype "bidirectional"))
      (node (ref "DS9") (pin "ANOT") (pinfunction "AN_ANOT") (pintype "bidirectional"))
      (node (ref "SWI9") (pin "MMR") (pinfunction "P2_MMR") (pintype "bidirectional"))
      (node (ref "SWI9") (pin "RCL") (pinfunction "P2_RCL") (pintype "bidirectional"))
      (node (ref "SWI9") (pin "RLMID") (pinfunction "P2_RLMID") (pintype "bidirectional"))
    )
    (net (code "23") (name "Net-(DS10-AN-PadANOST)") (class "Default")
      (node (ref "DS10") (pin "ANOST") (pinfunction "AN_ANOST") (pintype "bidirectional"))
      (node (ref "DS10") (pin "ANOT") (pinfunction "AN_ANOT") (pintype "bidirectional"))
      (node (ref "SWI10") (pin "MMR") (pinfunction "P2_MMR") (pintype "bidirectional"))
      (node (ref "SWI10") (pin "RCL") (pinfunction "P2_RCL") (pintype "bidirectional"))
      (node (ref "SWI10") (pin "RLMID") (pinfunction "P2_RLMID") (pintype "bidirectional"))
    )
    (net (code "24") (name "Net-(DS11-AN-PadANOST)") (class "Default")
      (node (ref "DS11") (pin "ANOST") (pinfunction "AN_ANOST") (pintype "bidirectional"))
      (node (ref "DS11") (pin "ANOT") (pinfunction "AN_ANOT") (pintype "bidirectional"))
      (node (ref "SWI11") (pin "MMR") (pinfunction "P2_MMR") (pintype "bidirectional"))
      (node (ref "SWI11") (pin "RCL") (pinfunction "P2_RCL") (pintype "bidirectional"))
      (node (ref "SWI11") (pin "RLMID") (pinfunction "P2_RLMID") (pintype "bidirectional"))
    )
    (net (code "25") (name "Net-(DS12-AN-PadANOST)") (class "Default")
      (node (ref "DS12") (pin "ANOST") (pinfunction "AN_ANOST") (pintype "bidirectional"))
      (node (ref "DS12") (pin "ANOT") (pinfunction "AN_ANOT") (pintype "bidirectional"))
      (node (ref "SWI12") (pin "MMR") (pinfunction "P2_MMR") (pintype "bidirectional"))
      (node (ref "SWI12") (pin "RCL") (pinfunction "P2_RCL") (pintype "bidirectional"))
      (node (ref "SWI12") (pin "RLMID") (pinfunction "P2_RLMID") (pintype "bidirectional"))
    )
    (net (code "26") (name "Net-(DS13-AN-PadANOST)") (class "Default")
      (node (ref "DS13") (pin "ANOST") (pinfunction "AN_ANOST") (pintype "bidirectional"))
      (node (ref "DS13") (pin "ANOT") (pinfunction "AN_ANOT") (pintype "bidirectional"))
      (node (ref "SWI13") (pin "MMR") (pinfunction "P2_MMR") (pintype "bidirectional"))
      (node (ref "SWI13") (pin "RCL") (pinfunction "P2_RCL") (pintype "bidirectional"))
      (node (ref "SWI13") (pin "RLMID") (pinfunction "P2_RLMID") (pintype "bidirectional"))
    )
    (net (code "27") (name "Net-(DS14-AN-PadANOST)") (class "Default")
      (node (ref "DS14") (pin "ANOST") (pinfunction "AN_ANOST") (pintype "bidirectional"))
      (node (ref "DS14") (pin "ANOT") (pinfunction "AN_ANOT") (pintype "bidirectional"))
      (node (ref "SWI14") (pin "MMR") (pinfunction "P2_MMR") (pintype "bidirectional"))
      (node (ref "SWI14") (pin "RCL") (pinfunction "P2_RCL") (pintype "bidirectional"))
      (node (ref "SWI14") (pin "RLMID") (pinfunction "P2_RLMID") (pintype "bidirectional"))
    )
    (net (code "28") (name "Net-(DS15-AN-PadANOST)") (class "Default")
      (node (ref "DS15") (pin "ANOST") (pinfunction "AN_ANOST") (pintype "bidirectional"))
      (node (ref "DS15") (pin "ANOT") (pinfunction "AN_ANOT") (pintype "bidirectional"))
      (node (ref "SWI15") (pin "MMR") (pinfunction "P2_MMR") (pintype "bidirectional"))
      (node (ref "SWI15") (pin "RCL") (pinfunction "P2_RCL") (pintype "bidirectional"))
      (node (ref "SWI15") (pin "RLMID") (pinfunction "P2_RLMID") (pintype "bidirectional"))
    )
    (net (code "29") (name "Net-(DS16-AN-PadANOST)") (class "Default")
      (node (ref "DS16") (pin "ANOST") (pinfunction "AN_ANOST") (pintype "bidirectional"))
      (node (ref "DS16") (pin "ANOT") (pinfunction "AN_ANOT") (pintype "bidirectional"))
      (node (ref "SWI16") (pin "MMR") (pinfunction "P2_MMR") (pintype "bidirectional"))
      (node (ref "SWI16") (pin "RCL") (pinfunction "P2_RCL") (pintype "bidirectional"))
      (node (ref "SWI16") (pin "RLMID") (pinfunction "P2_RLMID") (pintype "bidirectional"))
    )
    (net (code "30") (name "Net-(DS17-AN-PadANOST)") (class "Default")
      (node (ref "DS17") (pin "ANOST") (pinfunction "AN_ANOST") (pintype "bidirectional"))
      (node (ref "DS17") (pin "ANOT") (pinfunction "AN_ANOT") (pintype "bidirectional"))
      (node (ref "SWI17") (pin "MMR") (pinfunction "P2_MMR") (pintype "bidirectional"))
      (node (ref "SWI17") (pin "RCL") (pinfunction "P2_RCL") (pintype "bidirectional"))
      (node (ref "SWI17") (pin "RLMID") (pinfunction "P2_RLMID") (pintype "bidirectional"))
    )
    (net (code "31") (name "Net-(DS18-AN-PadANOST)") (class "Default")
      (node (ref "DS18") (pin "ANOST") (pinfunction "AN_ANOST") (pintype "bidirectional"))
      (node (ref "DS18") (pin "ANOT") (pinfunction "AN_ANOT") (pintype "bidirectional"))
      (node (ref "SWI18") (pin "MMR") (pinfunction "P2_MMR") (pintype "bidirectional"))
      (node (ref "SWI18") (pin "RCL") (pinfunction "P2_RCL") (pintype "bidirectional"))
      (node (ref "SWI18") (pin "RLMID") (pinfunction "P2_RLMID") (pintype "bidirectional"))
    )
    (net (code "32") (name "Net-(J1-CC1)") (class "Default")
      (node (ref "J1") (pin "A5") (pinfunction "CC1_A5") (pintype "bidirectional"))
      (node (ref "J1") (pin "B5") (pinfunction "CC2_B5") (pintype "bidirectional"))
      (node (ref "R1") (pin "2") (pinfunction "2_2") (pintype "passive"))
    )
    (net (code "33") (name "Net-(LED1-PadC)") (class "Default")
      (node (ref "LED1") (pin "C") (pinfunction "C_C") (pintype "passive"))
      (node (ref "R2") (pin "1") (pinfunction "1_1") (pintype "passive"))
    )
    (net (code "34") (name "Net-(R7-Pad1)") (class "Default")
      (node (ref "R7") (pin "1") (pinfunction "1_1") (pintype "passive"))
      (node (ref "SW3") (pin "COMM") (pinfunction "COMM_COMM") (pintype "passive"))
      (node (ref "U3") (pin "VIN") (pinfunction "VIN_VIN") (pintype "power_in"))
    )
    (net (code "35") (name "Net-(R7-Pad2)") (class "Default")
      (node (ref "R7") (pin "2") (pinfunction "2_2") (pintype "passive"))
      (node (ref "U3") (pin "CTRL") (pinfunction "CTRL_CTRL") (pintype "passive"))
    )
    (net (code "36") (name "Net-(U2-PROG)") (class "Default")
      (node (ref "R3") (pin "2") (pinfunction "2_2") (pintype "passive"))
      (node (ref "U2") (pin "5") (pinfunction "PROG_5") (pintype "passive"))
    )
    (net (code "37") (name "Net-(U2-STAT)") (class "Default")
      (node (ref "R2") (pin "2") (pinfunction "2_2") (pintype "passive"))
      (node (ref "U2") (pin "1") (pinfunction "STAT_1") (pintype "passive"))
    )
    (net (code "38") (name "Net-(U4-RST)") (class "Default")
      (node (ref "R8") (pin "2") (pinfunction "2_2") (pintype "passive"))
      (node (ref "U4") (pin "9") (pinfunction "RST_9") (pintype "input"))
    )
    (net (code "39") (name "Net-(U4-VBUS)") (class "Default")
      (node (ref "R10") (pin "2") (pinfunction "2_2") (pintype "passive"))
      (node (ref "R9") (pin "1") (pinfunction "1_1") (pintype "passive"))
      (node (ref "U4") (pin "8") (pinfunction "VBUS_8") (pintype "power_in"))
    )
    (net (code "40") (name "RESET") (class "Default")
      (node (ref "SW1") (pin "A1") (pinfunction "P$1_A1") (pintype "bidirectional"))
      (node (ref "SW1") (pin "A2") (pinfunction "P$1_A2") (pintype "bidirectional"))
      (node (ref "SW1") (pin "A3") (pinfunction "P$1_A3") (pintype "bidirectional"))
      (node (ref "SW1") (pin "A4") (pinfunction "P$1_A4") (pintype "bidirectional"))
      (node (ref "U1") (pin "7") (pinfunction "~{NRESET}_7") (pintype "input"))
    )
    (net (code "41") (name "ROW1") (class "Default")
      (node (ref "DS1") (pin "CATST") (pinfunction "CAT_CATST") (pintype "bidirectional"))
      (node (ref "DS1") (pin "CATT") (pinfunction "CAT_CATT") (pintype "bidirectional"))
      (node (ref "DS10") (pin "CATST") (pinfunction "CAT_CATST") (pintype "bidirectional"))
      (node (ref "DS10") (pin "CATT") (pinfunction "CAT_CATT") (pintype "bidirectional"))
      (node (ref "DS13") (pin "CATST") (pinfunction "CAT_CATST") (pintype "bidirectional"))
      (node (ref "DS13") (pin "CATT") (pinfunction "CAT_CATT") (pintype "bidirectional"))
      (node (ref "DS16") (pin "CATST") (pinfunction "CAT_CATST") (pintype "bidirectional"))
      (node (ref "DS16") (pin "CATT") (pinfunction "CAT_CATT") (pintype "bidirectional"))
      (node (ref "DS4") (pin "CATST") (pinfunction "CAT_CATST") (pintype "bidirectional"))
      (node (ref "DS4") (pin "CATT") (pinfunction "CAT_CATT") (pintype "bidirectional"))
      (node (ref "DS7") (pin "CATST") (pinfunction "CAT_CATST") (pintype "bidirectional"))
      (node (ref "DS7") (pin "CATT") (pinfunction "CAT_CATT") (pintype "bidirectional"))
      (node (ref "U1") (pin "2") (pinfunction "SIO_24/SPI_MISO_2") (pintype "bidirectional"))
    )
    (net (code "42") (name "ROW2") (class "Default")
      (node (ref "DS11") (pin "CATST") (pinfunction "CAT_CATST") (pintype "bidirectional"))
      (node (ref "DS11") (pin "CATT") (pinfunction "CAT_CATT") (pintype "bidirectional"))
      (node (ref "DS14") (pin "CATST") (pinfunction "CAT_CATST") (pintype "bidirectional"))
      (node (ref "DS14") (pin "CATT") (pinfunction "CAT_CATT") (pintype "bidirectional"))
      (node (ref "DS17") (pin "CATST") (pinfunction "CAT_CATST") (pintype "bidirectional"))
      (node (ref "DS17") (pin "CATT") (pinfunction "CAT_CATT") (pintype "bidirectional"))
      (node (ref "DS2") (pin "CATST") (pinfunction "CAT_CATST") (pintype "bidirectional"))
      (node (ref "DS2") (pin "CATT") (pinfunction "CAT_CATT") (pintype "bidirectional"))
      (node (ref "DS5") (pin "CATST") (pinfunction "CAT_CATST") (pintype "bidirectional"))
      (node (ref "DS5") (pin "CATT") (pinfunction "CAT_CATT") (pintype "bidirectional"))
      (node (ref "DS8") (pin "CATST") (pinfunction "CAT_CATST") (pintype "bidirectional"))
      (node (ref "DS8") (pin "CATT") (pinfunction "CAT_CATT") (pintype "bidirectional"))
      (node (ref "U1") (pin "38") (pinfunction "SIO_25/SPI_CLK_38") (pintype "bidirectional"))
    )
    (net (code "43") (name "ROW3") (class "Default")
      (node (ref "DS12") (pin "CATST") (pinfunction "CAT_CATST") (pintype "bidirectional"))
      (node (ref "DS12") (pin "CATT") (pinfunction "CAT_CATT") (pintype "bidirectional"))
      (node (ref "DS15") (pin "CATST") (pinfunction "CAT_CATST") (pintype "bidirectional"))
      (node (ref "DS15") (pin "CATT") (pinfunction "CAT_CATT") (pintype "bidirectional"))
      (node (ref "DS18") (pin "CATST") (pinfunction "CAT_CATST") (pintype "bidirectional"))
      (node (ref "DS18") (pin "CATT") (pinfunction "CAT_CATT") (pintype "bidirectional"))
      (node (ref "DS3") (pin "CATST") (pinfunction "CAT_CATST") (pintype "bidirectional"))
      (node (ref "DS3") (pin "CATT") (pinfunction "CAT_CATT") (pintype "bidirectional"))
      (node (ref "DS6") (pin "CATST") (pinfunction "CAT_CATST") (pintype "bidirectional"))
      (node (ref "DS6") (pin "CATT") (pinfunction "CAT_CATT") (pintype "bidirectional"))
      (node (ref "DS9") (pin "CATST") (pinfunction "CAT_CATST") (pintype "bidirectional"))
      (node (ref "DS9") (pin "CATT") (pinfunction "CAT_CATT") (pintype "bidirectional"))
      (node (ref "U1") (pin "37") (pinfunction "SIO_26/I2C_SDA_37") (pintype "bidirectional"))
    )
    (net (code "44") (name "ROW4") (class "Default")
      (node (ref "U1") (pin "36") (pinfunction "SIO_27/I2C_SCL_36") (pintype "bidirectional"))
    )
    (net (code "45") (name "ROW5T1") (class "Default")
      (node (ref "INT1") (pin "T1") (pinfunction "T1_T1") (pintype "bidirectional"))
      (node (ref "U1") (pin "35") (pinfunction "SIO_28/AIN4_35") (pintype "bidirectional"))
    )
    (net (code "46") (name "ROW6T2") (class "Default")
      (node (ref "INT1") (pin "T2") (pinfunction "T2_T2") (pintype "bidirectional"))
      (node (ref "U1") (pin "34") (pinfunction "SIO_29/AIN5_34") (pintype "bidirectional"))
    )
    (net (code "47") (name "RX0") (class "Default")
      (node (ref "J3") (pin "5") (pinfunction "5_5") (pintype "passive"))
      (node (ref "U1") (pin "17") (pinfunction "SIO_08/UART_RX_17") (pintype "bidirectional"))
      (node (ref "U4") (pin "17") (pinfunction "RXD_17") (pintype "input"))
    )
    (net (code "48") (name "SWDCLK") (class "Default")
      (node (ref "J2") (pin "2") (pinfunction "2_2") (pintype "passive"))
      (node (ref "U1") (pin "6") (pinfunction "SWDCLK_6") (pintype "input"))
    )
    (net (code "49") (name "SWDIO") (class "Default")
      (node (ref "J2") (pin "3") (pinfunction "3_3") (pintype "passive"))
      (node (ref "U1") (pin "5") (pinfunction "SWDIO_5") (pintype "bidirectional"))
    )
    (net (code "50") (name "TX0") (class "Default")
      (node (ref "J3") (pin "4") (pinfunction "4_4") (pintype "passive"))
      (node (ref "U1") (pin "19") (pinfunction "SIO_06/UART_TX_19") (pintype "bidirectional"))
      (node (ref "U4") (pin "18") (pinfunction "TXD_18") (pintype "output"))
    )
    (net (code "51") (name "V_BATT") (class "Default")
      (node (ref "C2") (pin "1") (pinfunction "1_1") (pintype "passive"))
      (node (ref "JP1") (pin "1") (pinfunction "1_1") (pintype "passive"))
      (node (ref "R5") (pin "2") (pinfunction "2_2") (pintype "passive"))
      (node (ref "T1") (pin "C") (pinfunction "C_C") (pintype "passive"))
      (node (ref "U2") (pin "3") (pinfunction "VBAT_3") (pintype "passive"))
    )
    (net (code "52") (name "V_USB") (class "Default")
      (node (ref "D1") (pin "A") (pinfunction "A_A") (pintype "passive"))
      (node (ref "J1") (pin "A4") (pinfunction "VBUS_A4") (pintype "bidirectional"))
      (node (ref "J1") (pin "A9") (pinfunction "VBUS_A9") (pintype "bidirectional"))
      (node (ref "J1") (pin "B4") (pinfunction "VBUS_B4") (pintype "bidirectional"))
      (node (ref "J1") (pin "B9") (pinfunction "VBUS_B9") (pintype "bidirectional"))
      (node (ref "J3") (pin "3") (pinfunction "3_3") (pintype "passive"))
      (node (ref "LED1") (pin "A") (pinfunction "A_A") (pintype "passive"))
      (node (ref "R4") (pin "2") (pinfunction "2_2") (pintype "passive"))
      (node (ref "R9") (pin "2") (pinfunction "2_2") (pintype "passive"))
      (node (ref "T1") (pin "B") (pinfunction "B_B") (pintype "passive"))
      (node (ref "U2") (pin "4") (pinfunction "VDD_4") (pintype "passive"))
      (node (ref "U4") (pin "7") (pinfunction "VREGIN_7") (pintype "power_in"))
    )
    (net (code "53") (name "unconnected-(J3-Pad2)") (class "Default")
      (node (ref "J3") (pin "2") (pinfunction "2_2") (pintype "passive"))
    )
    (net (code "54") (name "unconnected-(J3-Pad6)") (class "Default")
      (node (ref "J3") (pin "6") (pinfunction "6_6") (pintype "passive"))
    )
    (net (code "55") (name "unconnected-(SW3-Pad2)") (class "Default")
      (node (ref "SW3") (pin "2") (pinfunction "2_2") (pintype "passive"))
    )
    (net (code "56") (name "unconnected-(U1-NFC1{slash}SIO_09-Pad15)") (class "Default")
      (node (ref "U1") (pin "15") (pinfunction "NFC1/SIO_09_15") (pintype "bidirectional"))
    )
    (net (code "57") (name "unconnected-(U1-NFC2{slash}SIO_10-Pad14)") (class "Default")
      (node (ref "U1") (pin "14") (pinfunction "NFC2/SIO_10_14") (pintype "bidirectional"))
    )
    (net (code "58") (name "unconnected-(U1-SIO_00{slash}XL1-Pad25)") (class "Default")
      (node (ref "U1") (pin "25") (pinfunction "SIO_00/XL1_25") (pintype "bidirectional"))
    )
    (net (code "59") (name "unconnected-(U1-SIO_01{slash}XL2-Pad24)") (class "Default")
      (node (ref "U1") (pin "24") (pinfunction "SIO_01/XL2_24") (pintype "bidirectional"))
    )
    (net (code "60") (name "unconnected-(U1-SIO_02{slash}AIN0-Pad23)") (class "Default")
      (node (ref "U1") (pin "23") (pinfunction "SIO_02/AIN0_23") (pintype "bidirectional"))
    )
    (net (code "61") (name "unconnected-(U1-SIO_03{slash}AIN1-Pad22)") (class "Default")
      (node (ref "U1") (pin "22") (pinfunction "SIO_03/AIN1_22") (pintype "bidirectional"))
    )
    (net (code "62") (name "unconnected-(U1-SIO_04{slash}AIN2-Pad21)") (class "Default")
      (node (ref "U1") (pin "21") (pinfunction "SIO_04/AIN2_21") (pintype "bidirectional"))
    )
    (net (code "63") (name "unconnected-(U1-SIO_05{slash}UART_RTS{slash}AIN3-Pad20)") (class "Default")
      (node (ref "U1") (pin "20") (pinfunction "SIO_05/UART_RTS/AIN3_20") (pintype "bidirectional"))
    )
    (net (code "64") (name "unconnected-(U1-SIO_07{slash}UART_CTS-Pad18)") (class "Default")
      (node (ref "U1") (pin "18") (pinfunction "SIO_07/UART_CTS_18") (pintype "bidirectional"))
    )
    (net (code "65") (name "unconnected-(U1-SIO_17-Pad30)") (class "Default")
      (node (ref "U1") (pin "30") (pinfunction "SIO_17_30") (pintype "bidirectional"))
    )
    (net (code "66") (name "unconnected-(U1-SIO_18-Pad9)") (class "Default")
      (node (ref "U1") (pin "9") (pinfunction "SIO_18_9") (pintype "bidirectional"))
    )
    (net (code "67") (name "unconnected-(U1-SIO_19-Pad31)") (class "Default")
      (node (ref "U1") (pin "31") (pinfunction "SIO_19_31") (pintype "bidirectional"))
    )
    (net (code "68") (name "unconnected-(U1-SIO_22-Pad4)") (class "Default")
      (node (ref "U1") (pin "4") (pinfunction "SIO_22_4") (pintype "bidirectional"))
    )
    (net (code "69") (name "unconnected-(U1-SIO_23{slash}SPI_MOSI-Pad3)") (class "Default")
      (node (ref "U1") (pin "3") (pinfunction "SIO_23/SPI_MOSI_3") (pintype "bidirectional"))
    )
    (net (code "70") (name "unconnected-(U1-SIO_30{slash}AIN6-Pad33)") (class "Default")
      (node (ref "U1") (pin "33") (pinfunction "SIO_30/AIN6_33") (pintype "bidirectional"))
    )
    (net (code "71") (name "unconnected-(U3-PadNC)") (class "Default")
      (node (ref "U3") (pin "NC") (pinfunction "NC_NC") (pintype "no_connect"))
    )
    (net (code "72") (name "unconnected-(U4-CTS-Pad15)") (class "Default")
      (node (ref "U4") (pin "15") (pinfunction "CTS_15") (pintype "input"))
    )
    (net (code "73") (name "unconnected-(U4-GPIO.0{slash}CLK-Pad2)") (class "Default")
      (node (ref "U4") (pin "2") (pinfunction "GPIO.0/CLK_2") (pintype "bidirectional"))
    )
    (net (code "74") (name "unconnected-(U4-GPIO.1{slash}RS485-Pad1)") (class "Default")
      (node (ref "U4") (pin "1") (pinfunction "GPIO.1/RS485_1") (pintype "bidirectional"))
    )
    (net (code "75") (name "unconnected-(U4-GPIO.2{slash}TXT-Pad20)") (class "Default")
      (node (ref "U4") (pin "20") (pinfunction "GPIO.2/TXT_20") (pintype "bidirectional"))
    )
    (net (code "76") (name "unconnected-(U4-GPIO.3{slash}RXT-Pad19)") (class "Default")
      (node (ref "U4") (pin "19") (pinfunction "GPIO.3/RXT_19") (pintype "bidirectional"))
    )
    (net (code "77") (name "unconnected-(U4-NC-Pad10)") (class "Default")
      (node (ref "U4") (pin "10") (pinfunction "NC_10") (pintype "no_connect"))
    )
    (net (code "78") (name "unconnected-(U4-RTS-Pad16)") (class "Default")
      (node (ref "U4") (pin "16") (pinfunction "RTS_16") (pintype "output"))
    )
    (net (code "79") (name "unconnected-(U4-SUSPEND-Pad14)") (class "Default")
      (node (ref "U4") (pin "14") (pinfunction "SUSPEND_14") (pintype "output"))
    )
    (net (code "80") (name "unconnected-(U4-SUSPENDB-Pad11)") (class "Default")
      (node (ref "U4") (pin "11") (pinfunction "SUSPENDB_11") (pintype "output"))
    )
    (net (code "81") (name "unconnected-(U4-WAKEUP-Pad13)") (class "Default")
      (node (ref "U4") (pin "13") (pinfunction "WAKEUP_13") (pintype "input"))
    )
  )
)
